# MAX487.net
KiCad netlist of a schematic drawn in Altium Designer
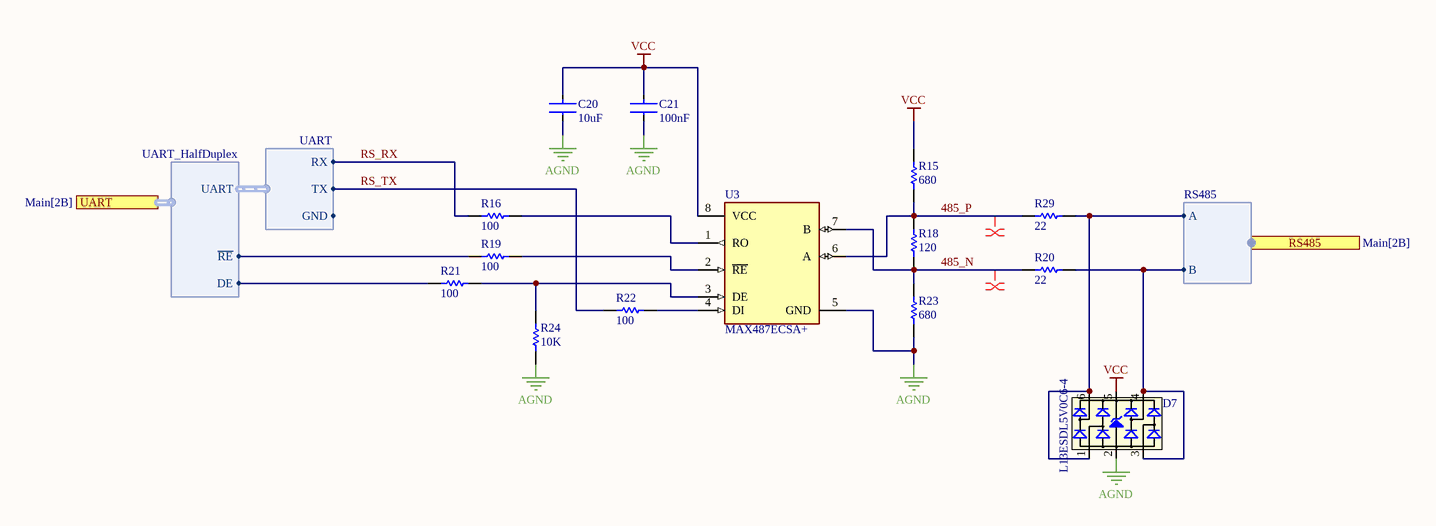
[diagram p0: MAX487.SchDoc]

(export (version "E")
  (design (tool "Eeschema 10.0.6"))
  (components
    (comp (ref "C20")
      (value "10uF")
      (footprint "Hosein_PCB_Lib_SMD:CAP-0603")
      (description "Chip Multilayer Ceramic Capacitors for General Purpose, 0603")
      (fields (field (name "VOLTAGE") "6.3V") (field (name "TOLERANCE") "20%"))
      (libsource (lib "Hosein_PCB_Lib") (part "CAP-Ceramic"))
    )
    (comp (ref "C21")
      (value "100nF")
      (footprint "Hosein_PCB_Lib_SMD:CAP-0603")
      (description "Chip Multilayer Ceramic Capacitors for General Purpose, 0603")
      (fields (field (name "VOLTAGE") "6.3V") (field (name "TOLERANCE") "20%"))
      (libsource (lib "Hosein_PCB_Lib") (part "CAP-Ceramic"))
    )
    (comp (ref "D7")
      (value "L13ESDL5V0C6-4")
      (footprint "SOT23_6L")
      (description "TVS Diode WE-TVS-HS, VRWM=5V")
      (libsource (lib "Altium Content Vault") (part "WE-TVS-HS-6_1"))
    )
    (comp (ref "R15")
      (value "680")
      (footprint "Hosein_PCB_Lib_SMD:RES-0603")
      (description "Chip Resistor")
      (fields (field (name "MANUFACTURER") "Vishay Semiconductor"))
      (libsource (lib "Hosein_PCB_Lib") (part "RES_SMD"))
    )
    (comp (ref "R16")
      (value "100")
      (footprint "Hosein_PCB_Lib_SMD:RES-0603")
      (description "Chip Resistor")
      (fields (field (name "MANUFACTURER") "Vishay Semiconductor"))
      (libsource (lib "Hosein_PCB_Lib") (part "RES_SMD"))
    )
    (comp (ref "R18")
      (value "120")
      (footprint "Hosein_PCB_Lib_SMD:RES-0603")
      (description "Chip Resistor")
      (fields (field (name "MANUFACTURER") "Vishay Semiconductor"))
      (libsource (lib "Hosein_PCB_Lib") (part "RES_SMD"))
    )
    (comp (ref "R19")
      (value "100")
      (footprint "Hosein_PCB_Lib_SMD:RES-0603")
      (description "Chip Resistor")
      (fields (field (name "MANUFACTURER") "Vishay Semiconductor"))
      (libsource (lib "Hosein_PCB_Lib") (part "RES_SMD"))
    )
    (comp (ref "R20")
      (value "22")
      (footprint "Hosein_PCB_Lib_SMD:RES-0603")
      (description "Chip Resistor")
      (fields (field (name "MANUFACTURER") "Vishay Semiconductor"))
      (libsource (lib "Hosein_PCB_Lib") (part "RES_SMD"))
    )
    (comp (ref "R21")
      (value "100")
      (footprint "Hosein_PCB_Lib_SMD:RES-0603")
      (description "Chip Resistor")
      (fields (field (name "MANUFACTURER") "Vishay Semiconductor"))
      (libsource (lib "Hosein_PCB_Lib") (part "RES_SMD"))
    )
    (comp (ref "R22")
      (value "100")
      (footprint "Hosein_PCB_Lib_SMD:RES-0603")
      (description "Chip Resistor")
      (fields (field (name "MANUFACTURER") "Vishay Semiconductor"))
      (libsource (lib "Hosein_PCB_Lib") (part "RES_SMD"))
    )
    (comp (ref "R23")
      (value "680")
      (footprint "Hosein_PCB_Lib_SMD:RES-0603")
      (description "Chip Resistor")
      (fields (field (name "MANUFACTURER") "Vishay Semiconductor"))
      (libsource (lib "Hosein_PCB_Lib") (part "RES_SMD"))
    )
    (comp (ref "R24")
      (value "10K")
      (footprint "Hosein_PCB_Lib_SMD:RES-0603")
      (description "Chip Resistor")
      (fields (field (name "MANUFACTURER") "Vishay Semiconductor"))
      (libsource (lib "Hosein_PCB_Lib") (part "RES_SMD"))
    )
    (comp (ref "R29")
      (value "22")
      (footprint "Hosein_PCB_Lib_SMD:RES-0603")
      (description "Chip Resistor")
      (fields (field (name "MANUFACTURER") "Vishay Semiconductor"))
      (libsource (lib "Hosein_PCB_Lib") (part "RES_SMD"))
    )
    (comp (ref "U3")
      (value "MAX487ECSA+")
      (footprint "FP-S8-5-MFG")
      (description "IC TXRX RS485/RS422 8-SOIC")
      (fields
        (field (name "OCTOPART") "https://octopart.com/max487ecsa%2B-maxim+integrated-39434994")
        (field (name "MANUFACTURER") "Maxim Integrated")
      )
      (libsource (lib "Altium Content Vault") (part "fda604458de2868cecf9c20fdddf798"))
    )
  )
  (nets
    (net (code "4") (name "/485_N") (class "Default")
      (node (ref "R18") (pin "1") (pinfunction "1_1") (pintype "passive"))
      (node (ref "R20") (pin "2") (pinfunction "2_2") (pintype "passive"))
      (node (ref "R23") (pin "2") (pinfunction "2_2") (pintype "passive"))
      (node (ref "U3") (pin "7") (pinfunction "B_7") (pintype "bidirectional"))
    )
    (net (code "5") (name "/485_P") (class "Default")
      (node (ref "R15") (pin "1") (pinfunction "1_1") (pintype "passive"))
      (node (ref "R18") (pin "2") (pinfunction "2_2") (pintype "passive"))
      (node (ref "R29") (pin "2") (pinfunction "2_2") (pintype "passive"))
      (node (ref "U3") (pin "6") (pinfunction "A_6") (pintype "bidirectional"))
    )
    (net (code "6") (name "/A") (class "Default")
      (node (ref "D7") (pin "1") (pinfunction "I/O1_1") (pintype "passive"))
      (node (ref "D7") (pin "6") (pinfunction "I/O4_6") (pintype "passive"))
      (node (ref "R29") (pin "1") (pinfunction "1_1") (pintype "passive"))
    )
    (net (code "7") (name "/B") (class "Default")
      (node (ref "D7") (pin "3") (pinfunction "I/O2_3") (pintype "passive"))
      (node (ref "D7") (pin "4") (pinfunction "I/O3_4") (pintype "passive"))
      (node (ref "R20") (pin "1") (pinfunction "1_1") (pintype "passive"))
    )
    (net (code "8") (name "/DE") (class "Default")
      (node (ref "R21") (pin "1") (pinfunction "1_1") (pintype "passive"))
    )
    (net (code "9") (name "/RS_RX") (class "Default")
      (node (ref "R16") (pin "1") (pinfunction "1_1") (pintype "passive"))
    )
    (net (code "10") (name "/RS_TX") (class "Default")
      (node (ref "R22") (pin "1") (pinfunction "1_1") (pintype "passive"))
    )
    (net (code "14") (name "/~{RE}") (class "Default")
      (node (ref "R19") (pin "1") (pinfunction "1_1") (pintype "passive"))
    )
    (net (code "15") (name "AGND") (class "Default")
      (node (ref "C20") (pin "2") (pinfunction "2_2") (pintype "passive"))
      (node (ref "C21") (pin "2") (pinfunction "2_2") (pintype "passive"))
      (node (ref "D7") (pin "2") (pinfunction "GND_2") (pintype "passive"))
      (node (ref "R23") (pin "1") (pinfunction "1_1") (pintype "passive"))
      (node (ref "R24") (pin "1") (pinfunction "1_1") (pintype "passive"))
      (node (ref "U3") (pin "5") (pinfunction "GND_5") (pintype "power_in"))
    )
    (net (code "16") (name "Net-(U3-DE)") (class "Default")
      (node (ref "R21") (pin "2") (pinfunction "2_2") (pintype "passive"))
      (node (ref "R24") (pin "2") (pinfunction "2_2") (pintype "passive"))
      (node (ref "U3") (pin "3") (pinfunction "DE_3") (pintype "input"))
    )
    (net (code "17") (name "Net-(U3-DI)") (class "Default")
      (node (ref "R22") (pin "2") (pinfunction "2_2") (pintype "passive"))
      (node (ref "U3") (pin "4") (pinfunction "DI_4") (pintype "input"))
    )
    (net (code "18") (name "Net-(U3-RO)") (class "Default")
      (node (ref "R16") (pin "2") (pinfunction "2_2") (pintype "passive"))
      (node (ref "U3") (pin "1") (pinfunction "RO_1") (pintype "output"))
    )
    (net (code "19") (name "Net-(U3-~{RE})") (class "Default")
      (node (ref "R19") (pin "2") (pinfunction "2_2") (pintype "passive"))
      (node (ref "U3") (pin "2") (pinfunction "~{RE}_2") (pintype "input"))
    )
    (net (code "20") (name "VCC") (class "Default")
      (node (ref "C20") (pin "1") (pinfunction "1_1") (pintype "passive"))
      (node (ref "C21") (pin "1") (pinfunction "1_1") (pintype "passive"))
      (node (ref "D7") (pin "5") (pinfunction "VDD_5") (pintype "passive"))
      (node (ref "R15") (pin "2") (pinfunction "2_2") (pintype "passive"))
      (node (ref "U3") (pin "8") (pinfunction "VCC_8") (pintype "power_in"))
    )
  )
)
